# Four_Monks_Expander_1_mix_lvl.net
KiCad netlist of a schematic drawn in EAGLE
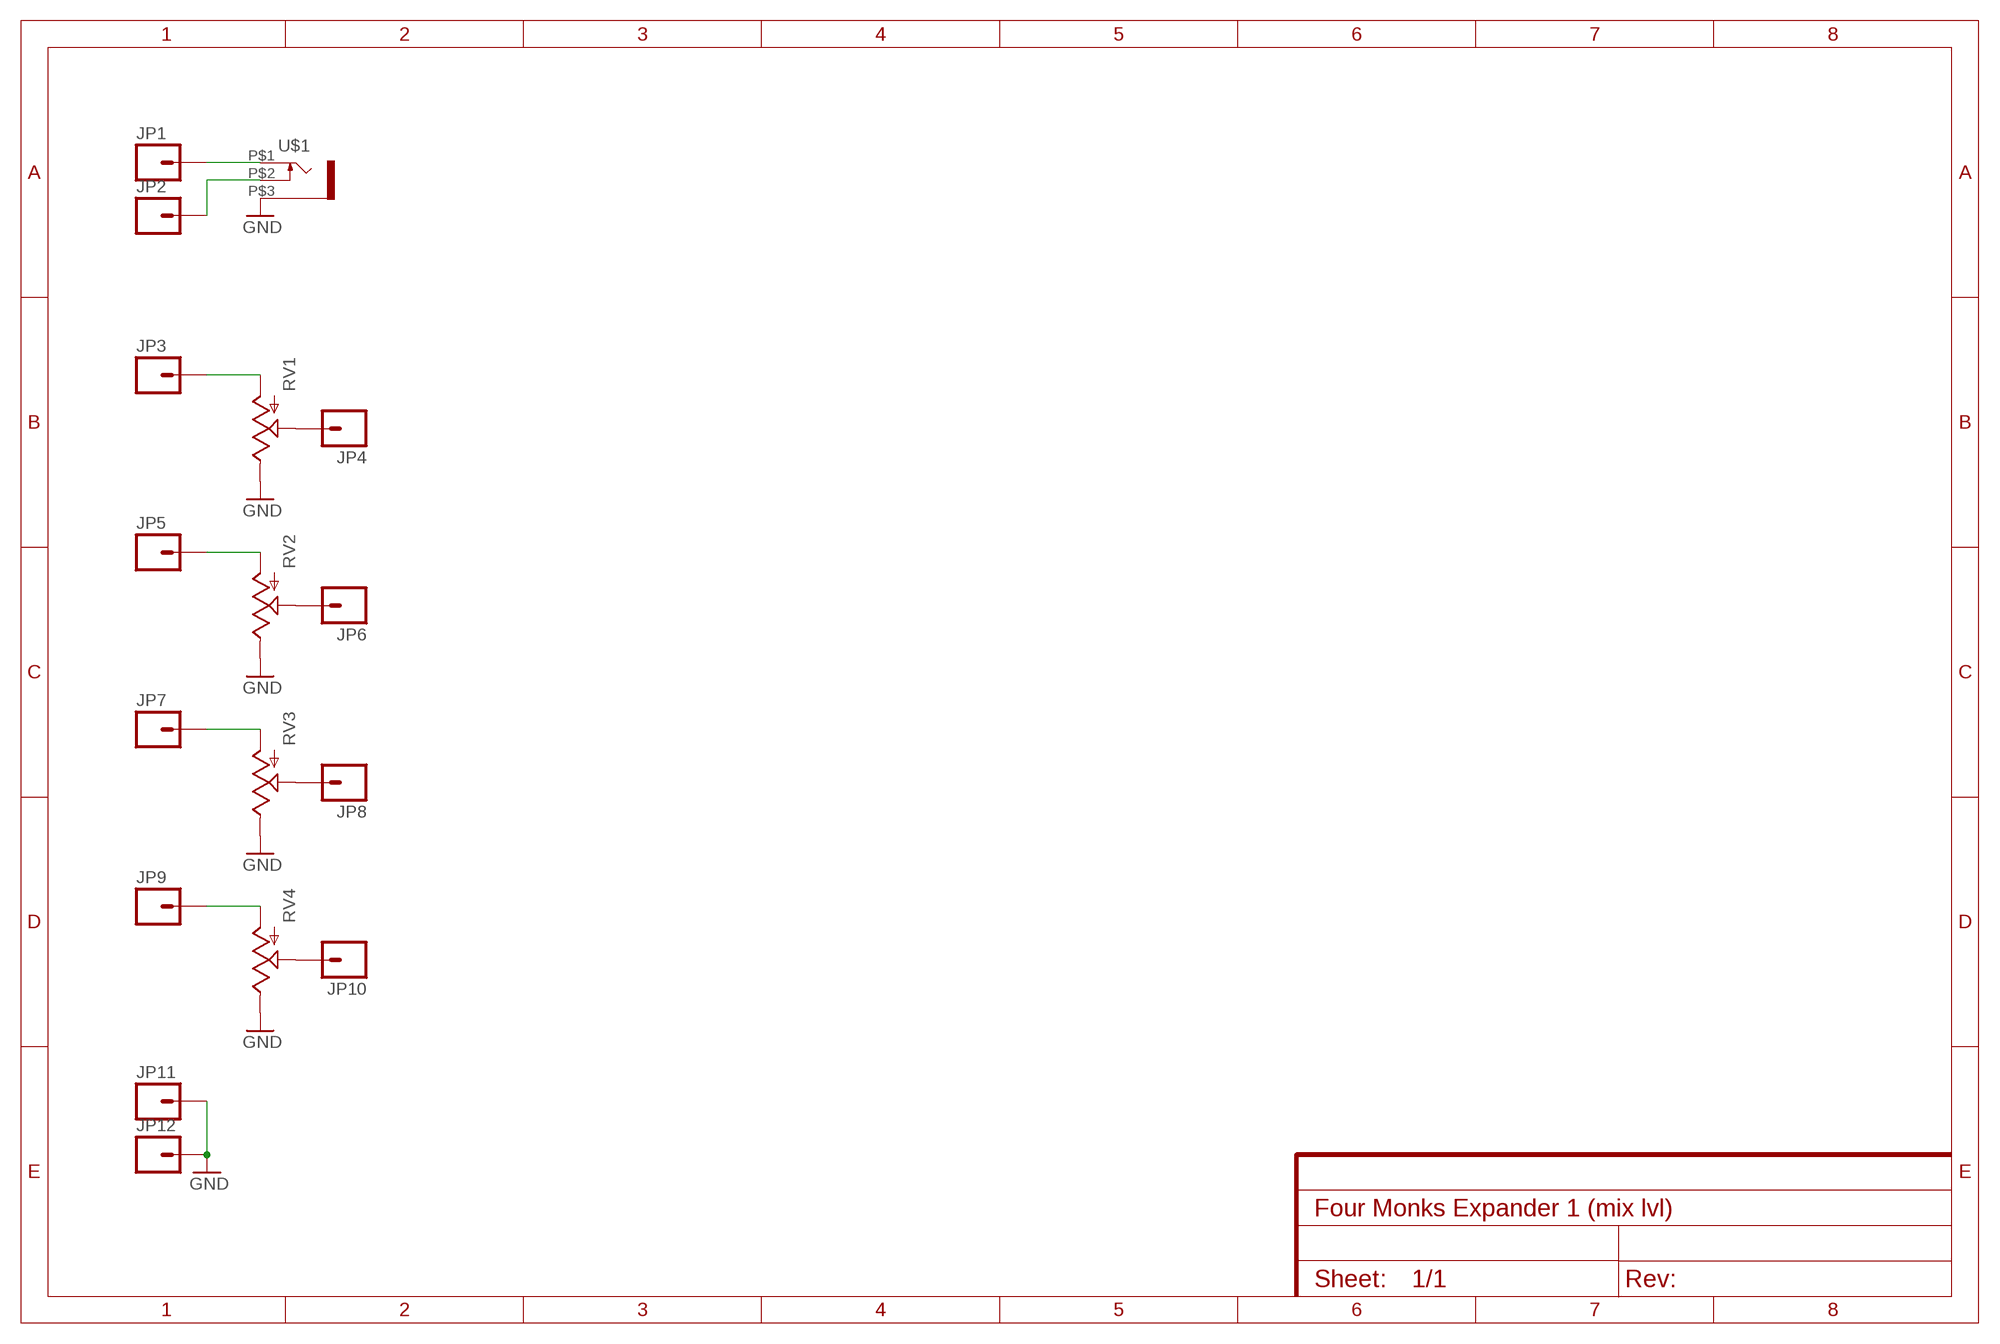
[diagram p0: schematic, sheet 1]

(export (version "E")
  (design (tool "Eeschema 10.0.6"))
  (components
    (comp (ref "JP1")
      (value "M01PTH")
      (footprint "eagle-import:1X01")
      (libsource (lib "eagle-import") (part "M01PTH"))
    )
    (comp (ref "JP2")
      (value "M01PTH")
      (footprint "eagle-import:1X01")
      (libsource (lib "eagle-import") (part "M01PTH"))
    )
    (comp (ref "JP3")
      (value "M01PTH")
      (footprint "eagle-import:1X01")
      (libsource (lib "eagle-import") (part "M01PTH"))
    )
    (comp (ref "JP4")
      (value "M01PTH")
      (footprint "eagle-import:1X01")
      (libsource (lib "eagle-import") (part "M01PTH"))
    )
    (comp (ref "JP5")
      (value "M01PTH")
      (footprint "eagle-import:1X01")
      (libsource (lib "eagle-import") (part "M01PTH"))
    )
    (comp (ref "JP6")
      (value "M01PTH")
      (footprint "eagle-import:1X01")
      (libsource (lib "eagle-import") (part "M01PTH"))
    )
    (comp (ref "JP7")
      (value "M01PTH")
      (footprint "eagle-import:1X01")
      (libsource (lib "eagle-import") (part "M01PTH"))
    )
    (comp (ref "JP8")
      (value "M01PTH")
      (footprint "eagle-import:1X01")
      (libsource (lib "eagle-import") (part "M01PTH"))
    )
    (comp (ref "JP9")
      (value "M01PTH")
      (footprint "eagle-import:1X01")
      (libsource (lib "eagle-import") (part "M01PTH"))
    )
    (comp (ref "JP10")
      (value "M01PTH")
      (footprint "eagle-import:1X01")
      (libsource (lib "eagle-import") (part "M01PTH"))
    )
    (comp (ref "JP11")
      (value "M01PTH")
      (footprint "eagle-import:1X01")
      (libsource (lib "eagle-import") (part "M01PTH"))
    )
    (comp (ref "JP12")
      (value "M01PTH")
      (footprint "eagle-import:1X01")
      (libsource (lib "eagle-import") (part "M01PTH"))
    )
    (comp (ref "RV1")
      (value "POT")
      (footprint "eagle-import:ALPS_POT")
      (libsource (lib "eagle-import") (part "POT"))
    )
    (comp (ref "RV2")
      (value "POT")
      (footprint "eagle-import:ALPS_POT")
      (libsource (lib "eagle-import") (part "POT"))
    )
    (comp (ref "RV3")
      (value "POT")
      (footprint "eagle-import:ALPS_POT")
      (libsource (lib "eagle-import") (part "POT"))
    )
    (comp (ref "RV4")
      (value "POT")
      (footprint "eagle-import:ALPS_POT")
      (libsource (lib "eagle-import") (part "POT"))
    )
    (comp (ref "U$1")
      (value "WQP-PJ301M-12_JACK")
      (footprint "eagle-import:WQP-PJ301M-12_JACK")
      (libsource (lib "eagle-import") (part "WQP-PJ301M-12_JACK"))
    )
  )
  (nets
    (net (code "1") (name "GND") (class "Default")
      (node (ref "JP11") (pin "1") (pinfunction "1_1") (pintype "passive"))
      (node (ref "JP12") (pin "1") (pinfunction "1_1") (pintype "passive"))
      (node (ref "RV1") (pin "P$1") (pinfunction "E_P$1") (pintype "passive"))
      (node (ref "RV2") (pin "P$1") (pinfunction "E_P$1") (pintype "passive"))
      (node (ref "RV3") (pin "P$1") (pinfunction "E_P$1") (pintype "passive"))
      (node (ref "RV4") (pin "P$1") (pinfunction "E_P$1") (pintype "passive"))
      (node (ref "U$1") (pin "P$3") (pinfunction "1_P$3") (pintype "passive"))
    )
    (net (code "2") (name "Net-(RV1-A)") (class "Default")
      (node (ref "JP3") (pin "1") (pinfunction "1_1") (pintype "passive"))
      (node (ref "RV1") (pin "P$3") (pinfunction "A_P$3") (pintype "passive"))
    )
    (net (code "3") (name "Net-(RV1-S)") (class "Default")
      (node (ref "JP4") (pin "1") (pinfunction "1_1") (pintype "passive"))
      (node (ref "RV1") (pin "P$2") (pinfunction "S_P$2") (pintype "passive"))
    )
    (net (code "4") (name "Net-(RV2-A)") (class "Default")
      (node (ref "JP5") (pin "1") (pinfunction "1_1") (pintype "passive"))
      (node (ref "RV2") (pin "P$3") (pinfunction "A_P$3") (pintype "passive"))
    )
    (net (code "5") (name "Net-(RV2-S)") (class "Default")
      (node (ref "JP6") (pin "1") (pinfunction "1_1") (pintype "passive"))
      (node (ref "RV2") (pin "P$2") (pinfunction "S_P$2") (pintype "passive"))
    )
    (net (code "6") (name "Net-(RV3-A)") (class "Default")
      (node (ref "JP7") (pin "1") (pinfunction "1_1") (pintype "passive"))
      (node (ref "RV3") (pin "P$3") (pinfunction "A_P$3") (pintype "passive"))
    )
    (net (code "7") (name "Net-(RV3-S)") (class "Default")
      (node (ref "JP8") (pin "1") (pinfunction "1_1") (pintype "passive"))
      (node (ref "RV3") (pin "P$2") (pinfunction "S_P$2") (pintype "passive"))
    )
    (net (code "8") (name "Net-(RV4-A)") (class "Default")
      (node (ref "JP9") (pin "1") (pinfunction "1_1") (pintype "passive"))
      (node (ref "RV4") (pin "P$3") (pinfunction "A_P$3") (pintype "passive"))
    )
    (net (code "9") (name "Net-(RV4-S)") (class "Default")
      (node (ref "JP10") (pin "1") (pinfunction "1_1") (pintype "passive"))
      (node (ref "RV4") (pin "P$2") (pinfunction "S_P$2") (pintype "passive"))
    )
    (net (code "10") (name "Net-(U$1-2)") (class "Default")
      (node (ref "JP1") (pin "1") (pinfunction "1_1") (pintype "passive"))
      (node (ref "U$1") (pin "P$1") (pinfunction "2_P$1") (pintype "passive"))
    )
    (net (code "11") (name "Net-(U$1-3)") (class "Default")
      (node (ref "JP2") (pin "1") (pinfunction "1_1") (pintype "passive"))
      (node (ref "U$1") (pin "P$2") (pinfunction "3_P$2") (pintype "passive"))
    )
  )
)
